# Pyr0-Piezo-FFC-Creality-X-Board_2_0_0.net
KiCad netlist of a schematic drawn in EAGLE
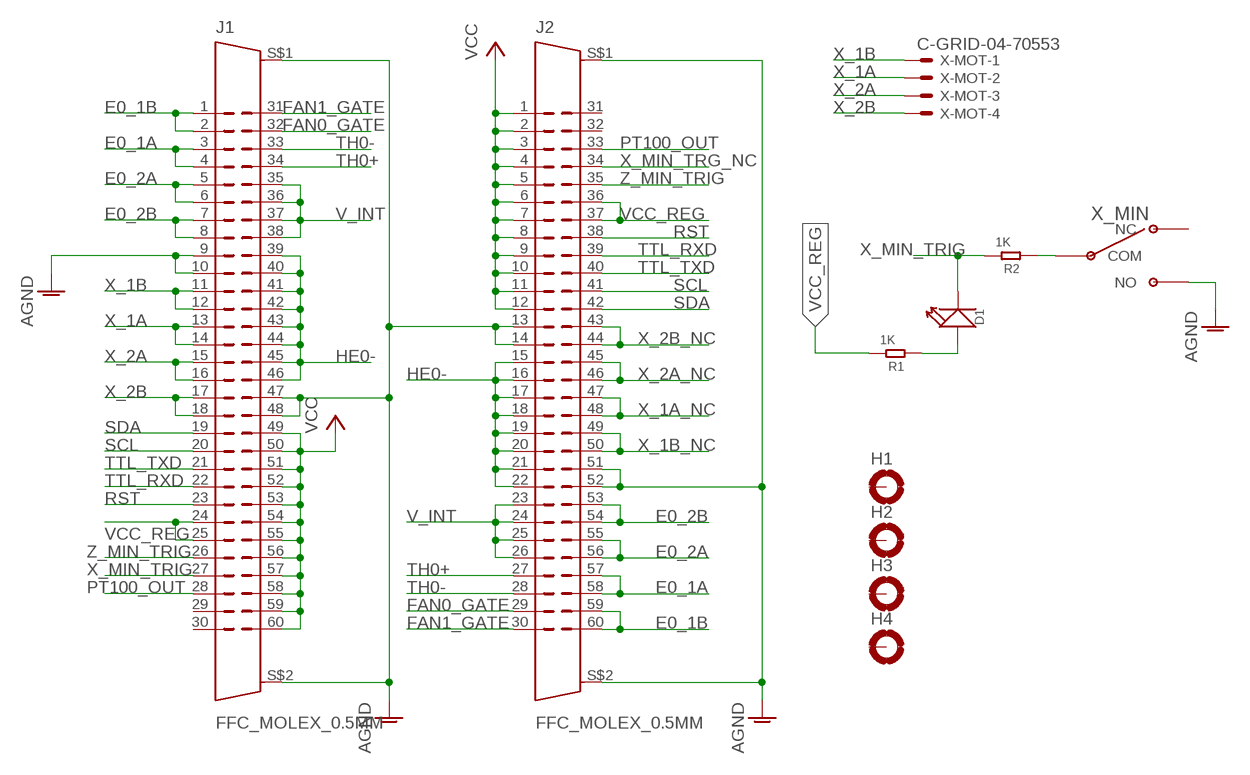
[diagram p0: schematic, sheet 1]

(export (version "E")
  (design (tool "Eeschema 10.0.6"))
  (components
    (comp (ref "D1")
      (value "SEEED-LED_SMD-LED-CLEAR-BLUE(0603)LED_0603")
      (footprint "eagle-import:SEEED-LED_LED-0603")
      (libsource (lib "eagle-import") (part "SEEED-LED_SMD-LED-CLEAR-BLUE(0603)LED_0603"))
    )
    (comp (ref "H1")
      (value "HOLES_MOUNT-PAD-ROUND3.2")
      (footprint "eagle-import:HOLES_3,2-PAD")
      (libsource (lib "eagle-import") (part "HOLES_MOUNT-PAD-ROUND3.2"))
    )
    (comp (ref "H2")
      (value "HOLES_MOUNT-PAD-ROUND3.2")
      (footprint "eagle-import:HOLES_3,2-PAD")
      (libsource (lib "eagle-import") (part "HOLES_MOUNT-PAD-ROUND3.2"))
    )
    (comp (ref "H3")
      (value "HOLES_MOUNT-PAD-ROUND3.2")
      (footprint "eagle-import:HOLES_3,2-PAD")
      (libsource (lib "eagle-import") (part "HOLES_MOUNT-PAD-ROUND3.2"))
    )
    (comp (ref "H4")
      (value "HOLES_MOUNT-PAD-ROUND3.2")
      (footprint "eagle-import:HOLES_3,2-PAD")
      (libsource (lib "eagle-import") (part "HOLES_MOUNT-PAD-ROUND3.2"))
    )
    (comp (ref "J1")
      (value "FFC_MOLEX_0.5MM")
      (footprint "eagle-import:FFC-60P_0.5_MOLEX_505110-6091")
      (libsource (lib "eagle-import") (part "FFC_MOLEX_0.5MM"))
    )
    (comp (ref "J2")
      (value "FFC_MOLEX_0.5MM")
      (footprint "eagle-import:FFC-60P_0.5_MOLEX_505110-6091")
      (libsource (lib "eagle-import") (part "FFC_MOLEX_0.5MM"))
    )
    (comp (ref "R1")
      (value "1K")
      (footprint "eagle-import:R0805")
      (fields (field (name "MPN") "RC0805JR-072KL"))
      (libsource (lib "eagle-import") (part "SMD-RES-2K-5%-1/8W(0805)"))
    )
    (comp (ref "R2")
      (value "1K")
      (footprint "eagle-import:R0805")
      (fields (field (name "MPN") "RC0805JR-072KL"))
      (libsource (lib "eagle-import") (part "SMD-RES-2K-5%-1/8W(0805)"))
    )
    (comp (ref "X-MOT")
      (value "C-GRID-04-70553")
      (footprint "eagle-import:70553-04")
      (fields (field (name "MF") "MOLEX"))
      (libsource (lib "eagle-import") (part "C-GRID-04-70553"))
    )
    (comp (ref "X_MIN")
      (value "LIMIT_SWITCHMICRO_SPDT_5.08")
      (footprint "eagle-import:MICROSWITCH_5.08")
      (libsource (lib "eagle-import") (part "LIMIT_SWITCHMICRO_SPDT_5.08"))
    )
  )
  (nets
    (net (code "1") (name "/E0_1A") (class "Default")
      (node (ref "J1") (pin "3") (pinfunction "5_3") (pintype "passive"))
      (node (ref "J1") (pin "4") (pinfunction "6_4") (pintype "passive"))
      (node (ref "J2") (pin "57") (pinfunction "63_57") (pintype "passive"))
      (node (ref "J2") (pin "58") (pinfunction "64_58") (pintype "passive"))
    )
    (net (code "2") (name "/E0_1B") (class "Default")
      (node (ref "J1") (pin "1") (pinfunction "3_1") (pintype "passive"))
      (node (ref "J1") (pin "2") (pinfunction "4_2") (pintype "passive"))
      (node (ref "J2") (pin "59") (pinfunction "65_59") (pintype "passive"))
      (node (ref "J2") (pin "60") (pinfunction "66_60") (pintype "passive"))
    )
    (net (code "3") (name "/E0_2A") (class "Default")
      (node (ref "J1") (pin "5") (pinfunction "7_5") (pintype "passive"))
      (node (ref "J1") (pin "6") (pinfunction "8_6") (pintype "passive"))
      (node (ref "J2") (pin "55") (pinfunction "61_55") (pintype "passive"))
      (node (ref "J2") (pin "56") (pinfunction "62_56") (pintype "passive"))
    )
    (net (code "4") (name "/E0_2B") (class "Default")
      (node (ref "J1") (pin "7") (pinfunction "9_7") (pintype "passive"))
      (node (ref "J1") (pin "8") (pinfunction "10_8") (pintype "passive"))
      (node (ref "J2") (pin "53") (pinfunction "59_53") (pintype "passive"))
      (node (ref "J2") (pin "54") (pinfunction "60_54") (pintype "passive"))
    )
    (net (code "5") (name "/FAN0_GATE") (class "Default")
      (node (ref "J1") (pin "32") (pinfunction "38_32") (pintype "passive"))
      (node (ref "J2") (pin "29") (pinfunction "31_29") (pintype "passive"))
    )
    (net (code "6") (name "/FAN1_GATE") (class "Default")
      (node (ref "J1") (pin "31") (pinfunction "37_31") (pintype "passive"))
      (node (ref "J2") (pin "30") (pinfunction "32_30") (pintype "passive"))
    )
    (net (code "7") (name "/HE0-") (class "Default")
      (node (ref "J1") (pin "39") (pinfunction "45_39") (pintype "passive"))
      (node (ref "J1") (pin "40") (pinfunction "46_40") (pintype "passive"))
      (node (ref "J1") (pin "41") (pinfunction "47_41") (pintype "passive"))
      (node (ref "J1") (pin "42") (pinfunction "48_42") (pintype "passive"))
      (node (ref "J1") (pin "43") (pinfunction "49_43") (pintype "passive"))
      (node (ref "J1") (pin "44") (pinfunction "50_44") (pintype "passive"))
      (node (ref "J1") (pin "45") (pinfunction "51_45") (pintype "passive"))
      (node (ref "J1") (pin "46") (pinfunction "52_46") (pintype "passive"))
      (node (ref "J2") (pin "15") (pinfunction "17_15") (pintype "passive"))
      (node (ref "J2") (pin "16") (pinfunction "18_16") (pintype "passive"))
      (node (ref "J2") (pin "17") (pinfunction "19_17") (pintype "passive"))
      (node (ref "J2") (pin "18") (pinfunction "20_18") (pintype "passive"))
      (node (ref "J2") (pin "19") (pinfunction "21_19") (pintype "passive"))
      (node (ref "J2") (pin "20") (pinfunction "22_20") (pintype "passive"))
      (node (ref "J2") (pin "21") (pinfunction "23_21") (pintype "passive"))
      (node (ref "J2") (pin "22") (pinfunction "24_22") (pintype "passive"))
    )
    (net (code "8") (name "/PT100_OUT") (class "Default")
      (node (ref "J1") (pin "28") (pinfunction "30_28") (pintype "passive"))
      (node (ref "J2") (pin "33") (pinfunction "39_33") (pintype "passive"))
    )
    (net (code "9") (name "/RST") (class "Default")
      (node (ref "J1") (pin "23") (pinfunction "25_23") (pintype "passive"))
      (node (ref "J2") (pin "38") (pinfunction "44_38") (pintype "passive"))
    )
    (net (code "10") (name "/SCL") (class "Default")
      (node (ref "J1") (pin "20") (pinfunction "22_20") (pintype "passive"))
      (node (ref "J2") (pin "41") (pinfunction "47_41") (pintype "passive"))
    )
    (net (code "11") (name "/SDA") (class "Default")
      (node (ref "J1") (pin "19") (pinfunction "21_19") (pintype "passive"))
      (node (ref "J2") (pin "42") (pinfunction "48_42") (pintype "passive"))
    )
    (net (code "12") (name "/TH0+") (class "Default")
      (node (ref "J1") (pin "34") (pinfunction "40_34") (pintype "passive"))
      (node (ref "J2") (pin "27") (pinfunction "29_27") (pintype "passive"))
    )
    (net (code "13") (name "/TH0-") (class "Default")
      (node (ref "J1") (pin "33") (pinfunction "39_33") (pintype "passive"))
      (node (ref "J2") (pin "28") (pinfunction "30_28") (pintype "passive"))
    )
    (net (code "14") (name "/TTL_RXD") (class "Default")
      (node (ref "J1") (pin "22") (pinfunction "24_22") (pintype "passive"))
      (node (ref "J2") (pin "39") (pinfunction "45_39") (pintype "passive"))
    )
    (net (code "15") (name "/TTL_TXD") (class "Default")
      (node (ref "J1") (pin "21") (pinfunction "23_21") (pintype "passive"))
      (node (ref "J2") (pin "40") (pinfunction "46_40") (pintype "passive"))
    )
    (net (code "16") (name "/V_INT") (class "Default")
      (node (ref "J1") (pin "35") (pinfunction "41_35") (pintype "passive"))
      (node (ref "J1") (pin "36") (pinfunction "42_36") (pintype "passive"))
      (node (ref "J1") (pin "37") (pinfunction "43_37") (pintype "passive"))
      (node (ref "J1") (pin "38") (pinfunction "44_38") (pintype "passive"))
      (node (ref "J2") (pin "23") (pinfunction "25_23") (pintype "passive"))
      (node (ref "J2") (pin "24") (pinfunction "26_24") (pintype "passive"))
      (node (ref "J2") (pin "25") (pinfunction "27_25") (pintype "passive"))
      (node (ref "J2") (pin "26") (pinfunction "28_26") (pintype "passive"))
    )
    (net (code "17") (name "/X_1A") (class "Default")
      (node (ref "J1") (pin "13") (pinfunction "15_13") (pintype "passive"))
      (node (ref "J1") (pin "14") (pinfunction "16_14") (pintype "passive"))
      (node (ref "X-MOT") (pin "2") (pinfunction "S_2") (pintype "passive"))
    )
    (net (code "18") (name "/X_1A_NC") (class "Default")
      (node (ref "J2") (pin "47") (pinfunction "53_47") (pintype "passive"))
      (node (ref "J2") (pin "48") (pinfunction "54_48") (pintype "passive"))
    )
    (net (code "19") (name "/X_1B") (class "Default")
      (node (ref "J1") (pin "11") (pinfunction "13_11") (pintype "passive"))
      (node (ref "J1") (pin "12") (pinfunction "14_12") (pintype "passive"))
      (node (ref "X-MOT") (pin "1") (pinfunction "S_1") (pintype "passive"))
    )
    (net (code "20") (name "/X_1B_NC") (class "Default")
      (node (ref "J2") (pin "49") (pinfunction "55_49") (pintype "passive"))
      (node (ref "J2") (pin "50") (pinfunction "56_50") (pintype "passive"))
    )
    (net (code "21") (name "/X_2A") (class "Default")
      (node (ref "J1") (pin "15") (pinfunction "17_15") (pintype "passive"))
      (node (ref "J1") (pin "16") (pinfunction "18_16") (pintype "passive"))
      (node (ref "X-MOT") (pin "3") (pinfunction "S_3") (pintype "passive"))
    )
    (net (code "22") (name "/X_2A_NC") (class "Default")
      (node (ref "J2") (pin "45") (pinfunction "51_45") (pintype "passive"))
      (node (ref "J2") (pin "46") (pinfunction "52_46") (pintype "passive"))
    )
    (net (code "23") (name "/X_2B") (class "Default")
      (node (ref "J1") (pin "17") (pinfunction "19_17") (pintype "passive"))
      (node (ref "J1") (pin "18") (pinfunction "20_18") (pintype "passive"))
      (node (ref "X-MOT") (pin "4") (pinfunction "S_4") (pintype "passive"))
    )
    (net (code "24") (name "/X_2B_NC") (class "Default")
      (node (ref "J2") (pin "43") (pinfunction "49_43") (pintype "passive"))
      (node (ref "J2") (pin "44") (pinfunction "50_44") (pintype "passive"))
    )
    (net (code "25") (name "/X_MIN_TRG_NC") (class "Default")
      (node (ref "J2") (pin "34") (pinfunction "40_34") (pintype "passive"))
    )
    (net (code "26") (name "/X_MIN_TRIG") (class "Default")
      (node (ref "D1") (pin "-") (pinfunction "-_-") (pintype "passive"))
      (node (ref "J1") (pin "27") (pinfunction "29_27") (pintype "passive"))
      (node (ref "R2") (pin "2") (pinfunction "2_2") (pintype "passive"))
    )
    (net (code "27") (name "/Z_MIN_TRIG") (class "Default")
      (node (ref "J1") (pin "26") (pinfunction "28_26") (pintype "passive"))
      (node (ref "J2") (pin "35") (pinfunction "41_35") (pintype "passive"))
    )
    (net (code "28") (name "AGND") (class "Default")
      (node (ref "J1") (pin "10") (pinfunction "12_10") (pintype "passive"))
      (node (ref "J1") (pin "47") (pinfunction "53_47") (pintype "passive"))
      (node (ref "J1") (pin "48") (pinfunction "54_48") (pintype "passive"))
      (node (ref "J1") (pin "9") (pinfunction "11_9") (pintype "passive"))
      (node (ref "J1") (pin "S$1") (pinfunction "S_S$1") (pintype "passive"))
      (node (ref "J1") (pin "S$2") (pinfunction "S_S$2") (pintype "passive"))
      (node (ref "J2") (pin "13") (pinfunction "15_13") (pintype "passive"))
      (node (ref "J2") (pin "14") (pinfunction "16_14") (pintype "passive"))
      (node (ref "J2") (pin "51") (pinfunction "57_51") (pintype "passive"))
      (node (ref "J2") (pin "52") (pinfunction "58_52") (pintype "passive"))
      (node (ref "J2") (pin "S$1") (pinfunction "S_S$1") (pintype "passive"))
      (node (ref "J2") (pin "S$2") (pinfunction "S_S$2") (pintype "passive"))
      (node (ref "X_MIN") (pin "P$2") (pinfunction "NO_P$2") (pintype "bidirectional"))
    )
    (net (code "29") (name "Net-(D1-Pad+)") (class "Default")
      (node (ref "D1") (pin "+") (pinfunction "+_+") (pintype "passive"))
      (node (ref "R1") (pin "1") (pinfunction "1_1") (pintype "passive"))
    )
    (net (code "30") (name "Net-(X_MIN-COM)") (class "Default")
      (node (ref "R2") (pin "1") (pinfunction "1_1") (pintype "passive"))
      (node (ref "X_MIN") (pin "P$1") (pinfunction "COM_P$1") (pintype "bidirectional"))
    )
    (net (code "31") (name "VCC") (class "Default")
      (node (ref "J1") (pin "49") (pinfunction "55_49") (pintype "passive"))
      (node (ref "J1") (pin "50") (pinfunction "56_50") (pintype "passive"))
      (node (ref "J1") (pin "51") (pinfunction "57_51") (pintype "passive"))
      (node (ref "J1") (pin "52") (pinfunction "58_52") (pintype "passive"))
      (node (ref "J1") (pin "53") (pinfunction "59_53") (pintype "passive"))
      (node (ref "J1") (pin "54") (pinfunction "60_54") (pintype "passive"))
      (node (ref "J1") (pin "55") (pinfunction "61_55") (pintype "passive"))
      (node (ref "J1") (pin "56") (pinfunction "62_56") (pintype "passive"))
      (node (ref "J1") (pin "57") (pinfunction "63_57") (pintype "passive"))
      (node (ref "J1") (pin "58") (pinfunction "64_58") (pintype "passive"))
      (node (ref "J1") (pin "59") (pinfunction "65_59") (pintype "passive"))
      (node (ref "J1") (pin "60") (pinfunction "66_60") (pintype "passive"))
      (node (ref "J2") (pin "1") (pinfunction "3_1") (pintype "passive"))
      (node (ref "J2") (pin "10") (pinfunction "12_10") (pintype "passive"))
      (node (ref "J2") (pin "11") (pinfunction "13_11") (pintype "passive"))
      (node (ref "J2") (pin "12") (pinfunction "14_12") (pintype "passive"))
      (node (ref "J2") (pin "2") (pinfunction "4_2") (pintype "passive"))
      (node (ref "J2") (pin "3") (pinfunction "5_3") (pintype "passive"))
      (node (ref "J2") (pin "4") (pinfunction "6_4") (pintype "passive"))
      (node (ref "J2") (pin "5") (pinfunction "7_5") (pintype "passive"))
      (node (ref "J2") (pin "6") (pinfunction "8_6") (pintype "passive"))
      (node (ref "J2") (pin "7") (pinfunction "9_7") (pintype "passive"))
      (node (ref "J2") (pin "8") (pinfunction "10_8") (pintype "passive"))
      (node (ref "J2") (pin "9") (pinfunction "11_9") (pintype "passive"))
    )
    (net (code "32") (name "VCC_REG") (class "Default")
      (node (ref "J1") (pin "24") (pinfunction "26_24") (pintype "passive"))
      (node (ref "J1") (pin "25") (pinfunction "27_25") (pintype "passive"))
      (node (ref "J2") (pin "36") (pinfunction "42_36") (pintype "passive"))
      (node (ref "J2") (pin "37") (pinfunction "43_37") (pintype "passive"))
      (node (ref "R1") (pin "2") (pinfunction "2_2") (pintype "passive"))
    )
    (net (code "33") (name "unconnected-(H1-MOUNT-PadB3,2)") (class "Default")
      (node (ref "H1") (pin "B3,2") (pinfunction "MOUNT_B3,2") (pintype "passive"))
    )
    (net (code "34") (name "unconnected-(H2-MOUNT-PadB3,2)") (class "Default")
      (node (ref "H2") (pin "B3,2") (pinfunction "MOUNT_B3,2") (pintype "passive"))
    )
    (net (code "35") (name "unconnected-(H3-MOUNT-PadB3,2)") (class "Default")
      (node (ref "H3") (pin "B3,2") (pinfunction "MOUNT_B3,2") (pintype "passive"))
    )
    (net (code "36") (name "unconnected-(H4-MOUNT-PadB3,2)") (class "Default")
      (node (ref "H4") (pin "B3,2") (pinfunction "MOUNT_B3,2") (pintype "passive"))
    )
    (net (code "37") (name "unconnected-(J1-31-Pad29)") (class "Default")
      (node (ref "J1") (pin "29") (pinfunction "31_29") (pintype "passive"))
    )
    (net (code "38") (name "unconnected-(J1-32-Pad30)") (class "Default")
      (node (ref "J1") (pin "30") (pinfunction "32_30") (pintype "passive"))
    )
    (net (code "39") (name "unconnected-(J2-37-Pad31)") (class "Default")
      (node (ref "J2") (pin "31") (pinfunction "37_31") (pintype "passive"))
    )
    (net (code "40") (name "unconnected-(J2-38-Pad32)") (class "Default")
      (node (ref "J2") (pin "32") (pinfunction "38_32") (pintype "passive"))
    )
    (net (code "41") (name "unconnected-(X_MIN-NC-PadP$3)") (class "Default")
      (node (ref "X_MIN") (pin "P$3") (pinfunction "NC_P$3") (pintype "bidirectional"))
    )
  )
)
